# Pi2RMini_1_0.net
KiCad netlist of a schematic drawn in EAGLE
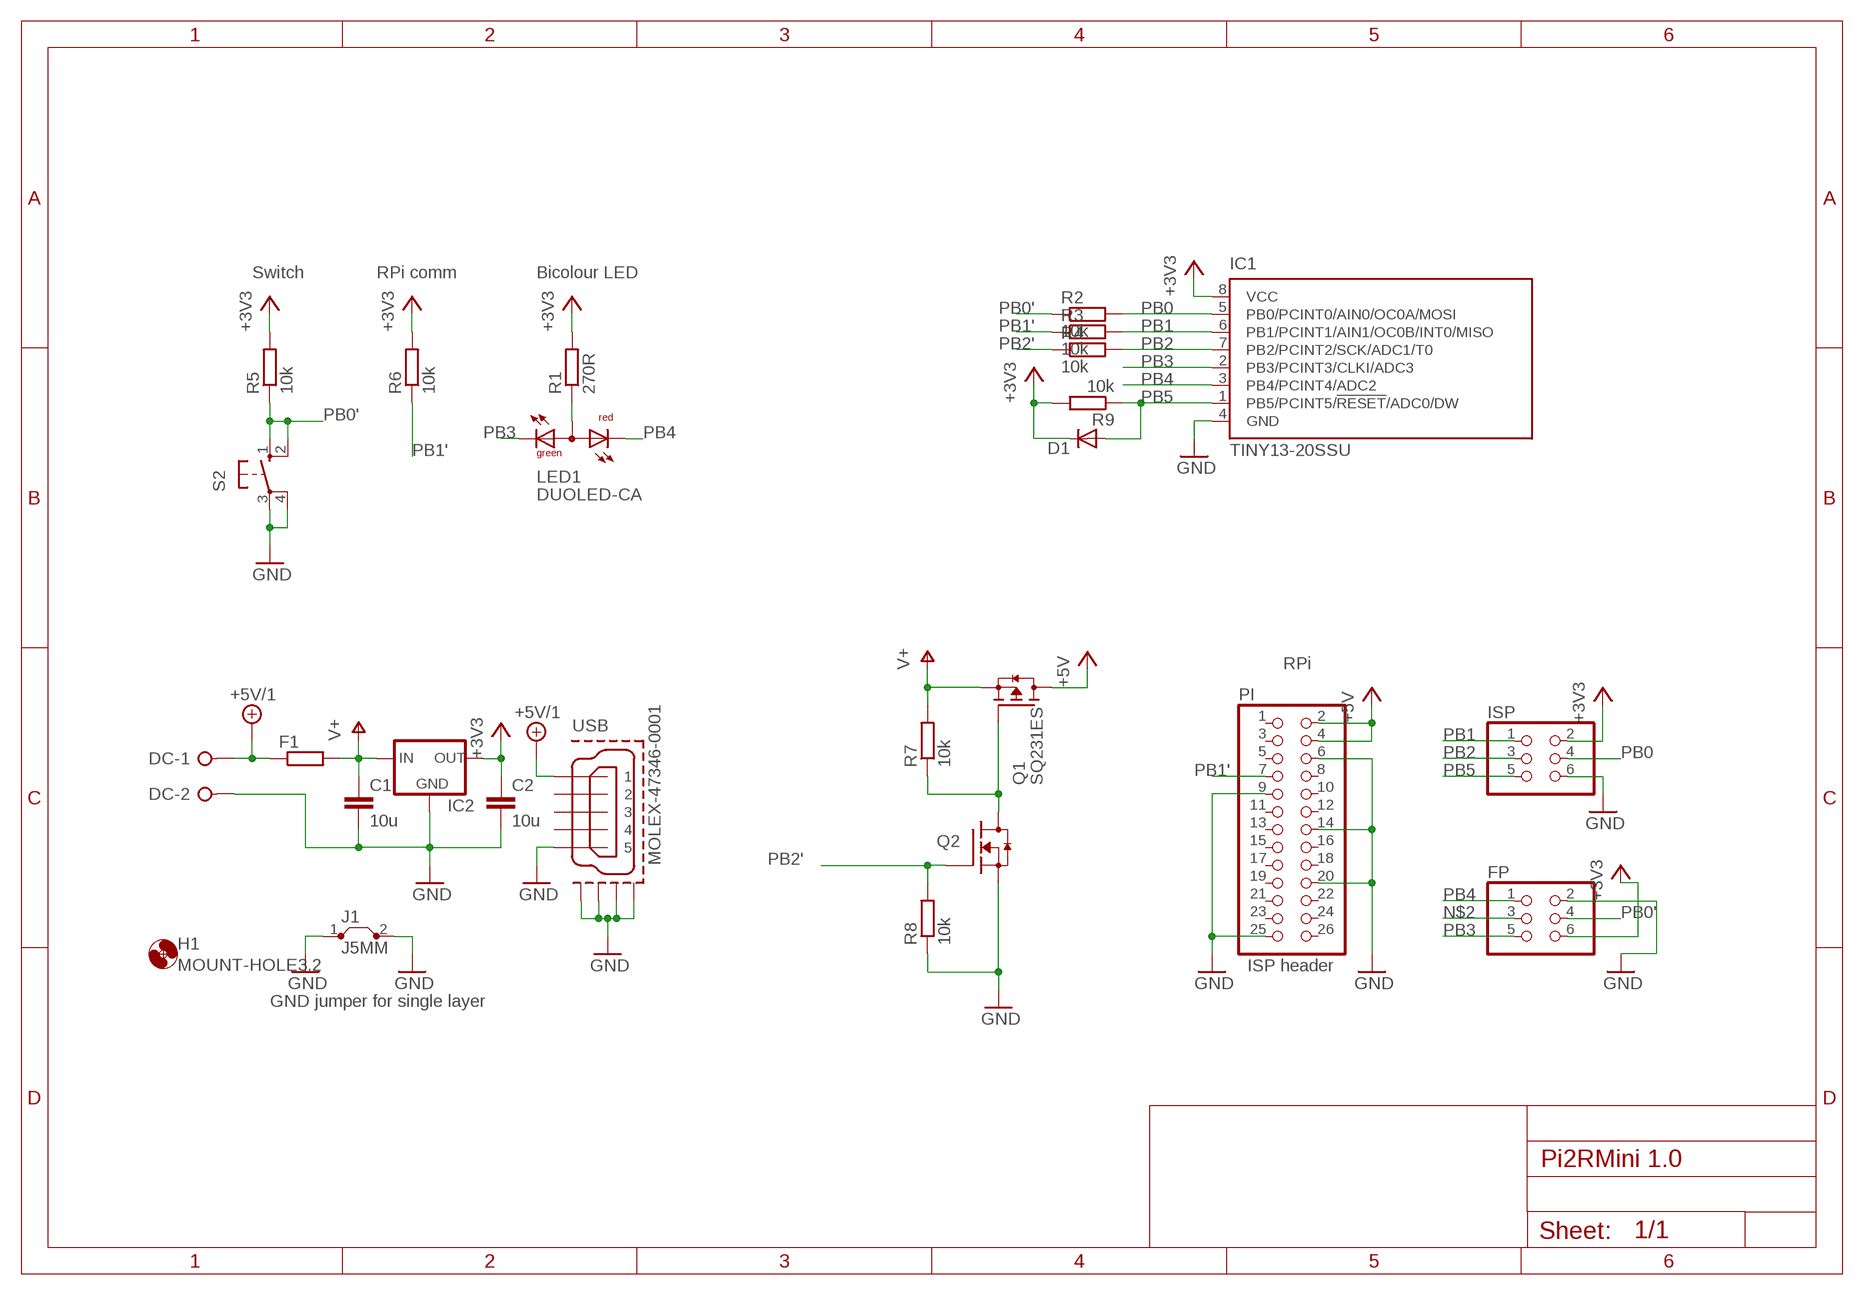
[diagram p0: schematic, sheet 1]

(export (version "E")
  (design (tool "Eeschema 10.0.6"))
  (components
    (comp (ref "C1")
      (value "10u")
      (footprint "eagle-import:C0805")
      (libsource (lib "eagle-import") (part "C-EUC0805"))
    )
    (comp (ref "C2")
      (value "10u")
      (footprint "eagle-import:C0805")
      (libsource (lib "eagle-import") (part "C-EUC0805"))
    )
    (comp (ref "D1")
      (value "DIODE-MICROMELF-R")
      (footprint "eagle-import:MICROMELF-R")
      (libsource (lib "eagle-import") (part "DIODE-MICROMELF-R"))
    )
    (comp (ref "DC")
      (value "W237-02P")
      (footprint "eagle-import:W237-132")
      (libsource (lib "eagle-import") (part "W237-02P"))
    )
    (comp (ref "F1")
      (value "R-EU_R1210")
      (footprint "eagle-import:R1210")
      (libsource (lib "eagle-import") (part "R-EU_R1210"))
    )
    (comp (ref "FP")
      (value "PINHD-2X3")
      (footprint "eagle-import:2X03")
      (libsource (lib "eagle-import") (part "PINHD-2X3"))
    )
    (comp (ref "H1")
      (value "MOUNT-HOLE3.2")
      (footprint "eagle-import:3,2")
      (libsource (lib "eagle-import") (part "MOUNT-HOLE3.2"))
    )
    (comp (ref "IC1")
      (value "TINY13-20SSU")
      (footprint "eagle-import:8S1")
      (fields (field (name "MPN") "ATTINY13-20SSU"))
      (libsource (lib "eagle-import") (part "TINY13SSU-20"))
    )
    (comp (ref "IC2")
      (value "MCP1700TT")
      (footprint "eagle-import:SOT-23")
      (libsource (lib "eagle-import") (part "MCP1700TT"))
    )
    (comp (ref "ISP")
      (value "PINHD-2X3")
      (footprint "eagle-import:2X03")
      (libsource (lib "eagle-import") (part "PINHD-2X3"))
    )
    (comp (ref "J1")
      (value "J5MM")
      (footprint "eagle-import:05")
      (libsource (lib "eagle-import") (part "J5MM"))
    )
    (comp (ref "LED1")
      (value "DUOLED-CA")
      (footprint "eagle-import:SOT-23")
      (libsource (lib "eagle-import") (part "DUOLED-CA"))
    )
    (comp (ref "PI")
      (value "PINHD-2X13")
      (footprint "eagle-import:2X13")
      (libsource (lib "eagle-import") (part "PINHD-2X13"))
    )
    (comp (ref "Q1")
      (value "SQ231ES")
      (footprint "eagle-import:SOT-23")
      (libsource (lib "eagle-import") (part "SQ231ES"))
    )
    (comp (ref "Q2")
      (value "2N7002")
      (footprint "eagle-import:SOT-23")
      (libsource (lib "eagle-import") (part "2N7002"))
    )
    (comp (ref "R1")
      (value "270R")
      (footprint "eagle-import:R0805")
      (libsource (lib "eagle-import") (part "R-EU_R0805"))
    )
    (comp (ref "R2")
      (value "10k")
      (footprint "eagle-import:R0805")
      (libsource (lib "eagle-import") (part "R-EU_R0805"))
    )
    (comp (ref "R3")
      (value "10k")
      (footprint "eagle-import:R0805")
      (libsource (lib "eagle-import") (part "R-EU_R0805"))
    )
    (comp (ref "R4")
      (value "10k")
      (footprint "eagle-import:R0805")
      (libsource (lib "eagle-import") (part "R-EU_R0805"))
    )
    (comp (ref "R5")
      (value "10k")
      (footprint "eagle-import:R0805")
      (libsource (lib "eagle-import") (part "R-EU_R0805"))
    )
    (comp (ref "R6")
      (value "10k")
      (footprint "eagle-import:R0805")
      (libsource (lib "eagle-import") (part "R-EU_R0805"))
    )
    (comp (ref "R7")
      (value "10k")
      (footprint "eagle-import:R0805")
      (libsource (lib "eagle-import") (part "R-EU_R0805"))
    )
    (comp (ref "R8")
      (value "10k")
      (footprint "eagle-import:R0805")
      (libsource (lib "eagle-import") (part "R-EU_R0805"))
    )
    (comp (ref "R9")
      (value "10k")
      (footprint "eagle-import:R0805")
      (libsource (lib "eagle-import") (part "R-EU_R0805"))
    )
    (comp (ref "S2")
      (value "10-XX")
      (footprint "eagle-import:B3F-10XX")
      (fields (field (name "MPN") "B3F-1000"))
      (libsource (lib "eagle-import") (part "10-XX"))
    )
    (comp (ref "USB")
      (value "MOLEX-47346-0001")
      (footprint "eagle-import:MOLEX-47364-0001")
      (libsource (lib "eagle-import") (part "MOLEX-47346-0001"))
    )
  )
  (nets
    (net (code "1") (name "+3V3") (class "Default")
      (node (ref "C2") (pin "1") (pinfunction "1_1") (pintype "passive"))
      (node (ref "D1") (pin "C") (pinfunction "C_C") (pintype "passive"))
      (node (ref "FP") (pin "6") (pinfunction "6_6") (pintype "passive"))
      (node (ref "IC1") (pin "8") (pinfunction "VCC_8") (pintype "power_in"))
      (node (ref "IC2") (pin "2") (pinfunction "OUT_2") (pintype "passive"))
      (node (ref "ISP") (pin "2") (pinfunction "2_2") (pintype "passive"))
      (node (ref "R1") (pin "2") (pinfunction "2_2") (pintype "passive"))
      (node (ref "R5") (pin "2") (pinfunction "2_2") (pintype "passive"))
      (node (ref "R6") (pin "2") (pinfunction "2_2") (pintype "passive"))
      (node (ref "R9") (pin "2") (pinfunction "2_2") (pintype "passive"))
    )
    (net (code "2") (name "+5V") (class "Default")
      (node (ref "PI") (pin "2") (pinfunction "2_2") (pintype "passive"))
      (node (ref "PI") (pin "4") (pinfunction "4_4") (pintype "passive"))
      (node (ref "Q1") (pin "3") (pinfunction "D_3") (pintype "passive"))
    )
    (net (code "3") (name "+5V{slash}1") (class "Default")
      (node (ref "DC") (pin "1") (pinfunction "KL_1") (pintype "passive"))
      (node (ref "F1") (pin "1") (pinfunction "1_1") (pintype "passive"))
      (node (ref "USB") (pin "1") (pinfunction "1_1") (pintype "input"))
    )
    (net (code "4") (name "/N$2") (class "Default")
      (node (ref "FP") (pin "3") (pinfunction "3_3") (pintype "passive"))
      (node (ref "LED1") (pin "3") (pinfunction "A_3") (pintype "passive"))
      (node (ref "R1") (pin "1") (pinfunction "1_1") (pintype "passive"))
    )
    (net (code "5") (name "/PB0") (class "Default")
      (node (ref "IC1") (pin "5") (pinfunction "PB0/PCINT0/AIN0/OC0A/MOSI_5") (pintype "bidirectional"))
      (node (ref "ISP") (pin "4") (pinfunction "4_4") (pintype "passive"))
      (node (ref "R2") (pin "2") (pinfunction "2_2") (pintype "passive"))
    )
    (net (code "6") (name "/PB0'") (class "Default")
      (node (ref "FP") (pin "4") (pinfunction "4_4") (pintype "passive"))
      (node (ref "R2") (pin "1") (pinfunction "1_1") (pintype "passive"))
      (node (ref "R5") (pin "1") (pinfunction "1_1") (pintype "passive"))
      (node (ref "S2") (pin "1") (pinfunction "S_1") (pintype "passive"))
      (node (ref "S2") (pin "2") (pinfunction "S1_2") (pintype "passive"))
    )
    (net (code "7") (name "/PB1") (class "Default")
      (node (ref "IC1") (pin "6") (pinfunction "PB1/PCINT1/AIN1/OC0B/INT0/MISO_6") (pintype "bidirectional"))
      (node (ref "ISP") (pin "1") (pinfunction "1_1") (pintype "passive"))
      (node (ref "R3") (pin "2") (pinfunction "2_2") (pintype "passive"))
    )
    (net (code "8") (name "/PB1'") (class "Default")
      (node (ref "PI") (pin "7") (pinfunction "7_7") (pintype "passive"))
      (node (ref "R3") (pin "1") (pinfunction "1_1") (pintype "passive"))
      (node (ref "R6") (pin "1") (pinfunction "1_1") (pintype "passive"))
    )
    (net (code "9") (name "/PB2") (class "Default")
      (node (ref "IC1") (pin "7") (pinfunction "PB2/PCINT2/SCK/ADC1/T0_7") (pintype "bidirectional"))
      (node (ref "ISP") (pin "3") (pinfunction "3_3") (pintype "passive"))
      (node (ref "R4") (pin "2") (pinfunction "2_2") (pintype "passive"))
    )
    (net (code "10") (name "/PB2'") (class "Default")
      (node (ref "Q2") (pin "1") (pinfunction "G_1") (pintype "passive"))
      (node (ref "R4") (pin "1") (pinfunction "1_1") (pintype "passive"))
      (node (ref "R8") (pin "2") (pinfunction "2_2") (pintype "passive"))
    )
    (net (code "11") (name "/PB3") (class "Default")
      (node (ref "FP") (pin "5") (pinfunction "5_5") (pintype "passive"))
      (node (ref "IC1") (pin "2") (pinfunction "PB3/PCINT3/CLKI/ADC3_2") (pintype "bidirectional"))
      (node (ref "LED1") (pin "2") (pinfunction "CG_2") (pintype "passive"))
    )
    (net (code "12") (name "/PB4") (class "Default")
      (node (ref "FP") (pin "1") (pinfunction "1_1") (pintype "passive"))
      (node (ref "IC1") (pin "3") (pinfunction "PB4/PCINT4/ADC2_3") (pintype "bidirectional"))
      (node (ref "LED1") (pin "1") (pinfunction "CR_1") (pintype "passive"))
    )
    (net (code "13") (name "/PB5") (class "Default")
      (node (ref "D1") (pin "A") (pinfunction "A_A") (pintype "passive"))
      (node (ref "IC1") (pin "1") (pinfunction "PB5/PCINT5/~{RESET}/ADC0/DW_1") (pintype "bidirectional"))
      (node (ref "ISP") (pin "5") (pinfunction "5_5") (pintype "passive"))
      (node (ref "R9") (pin "1") (pinfunction "1_1") (pintype "passive"))
    )
    (net (code "14") (name "GND") (class "Default")
      (node (ref "C1") (pin "2") (pinfunction "2_2") (pintype "passive"))
      (node (ref "C2") (pin "2") (pinfunction "2_2") (pintype "passive"))
      (node (ref "DC") (pin "2") (pinfunction "KL_2") (pintype "passive"))
      (node (ref "FP") (pin "2") (pinfunction "2_2") (pintype "passive"))
      (node (ref "IC1") (pin "4") (pinfunction "GND_4") (pintype "power_in"))
      (node (ref "IC2") (pin "1") (pinfunction "GND_1") (pintype "input"))
      (node (ref "ISP") (pin "6") (pinfunction "6_6") (pintype "passive"))
      (node (ref "J1") (pin "1") (pinfunction "1_1") (pintype "passive"))
      (node (ref "J1") (pin "2") (pinfunction "2_2") (pintype "passive"))
      (node (ref "PI") (pin "14") (pinfunction "14_14") (pintype "passive"))
      (node (ref "PI") (pin "20") (pinfunction "20_20") (pintype "passive"))
      (node (ref "PI") (pin "25") (pinfunction "25_25") (pintype "passive"))
      (node (ref "PI") (pin "6") (pinfunction "6_6") (pintype "passive"))
      (node (ref "PI") (pin "9") (pinfunction "9_9") (pintype "passive"))
      (node (ref "Q2") (pin "2") (pinfunction "S_2") (pintype "passive"))
      (node (ref "R8") (pin "1") (pinfunction "1_1") (pintype "passive"))
      (node (ref "S2") (pin "3") (pinfunction "P_3") (pintype "passive"))
      (node (ref "S2") (pin "4") (pinfunction "P1_4") (pintype "passive"))
      (node (ref "USB") (pin "5") (pinfunction "5_5") (pintype "input"))
      (node (ref "USB") (pin "GND1") (pinfunction "GND1_GND1") (pintype "bidirectional"))
      (node (ref "USB") (pin "GND2") (pinfunction "GND2_GND2") (pintype "bidirectional"))
      (node (ref "USB") (pin "GND3") (pinfunction "GND3_GND3") (pintype "bidirectional"))
      (node (ref "USB") (pin "GND4") (pinfunction "GND4_GND4") (pintype "bidirectional"))
    )
    (net (code "15") (name "Net-(Q1-G)") (class "Default")
      (node (ref "Q1") (pin "1") (pinfunction "G_1") (pintype "passive"))
      (node (ref "Q2") (pin "3") (pinfunction "D_3") (pintype "passive"))
      (node (ref "R7") (pin "1") (pinfunction "1_1") (pintype "passive"))
    )
    (net (code "16") (name "V+") (class "Default")
      (node (ref "C1") (pin "1") (pinfunction "1_1") (pintype "passive"))
      (node (ref "F1") (pin "2") (pinfunction "2_2") (pintype "passive"))
      (node (ref "IC2") (pin "3") (pinfunction "IN_3") (pintype "input"))
      (node (ref "Q1") (pin "2") (pinfunction "S_2") (pintype "passive"))
      (node (ref "R7") (pin "2") (pinfunction "2_2") (pintype "passive"))
    )
    (net (code "17") (name "unconnected-(PI-Pad1)") (class "Default")
      (node (ref "PI") (pin "1") (pinfunction "1_1") (pintype "passive"))
    )
    (net (code "18") (name "unconnected-(PI-Pad3)") (class "Default")
      (node (ref "PI") (pin "3") (pinfunction "3_3") (pintype "passive"))
    )
    (net (code "19") (name "unconnected-(PI-Pad5)") (class "Default")
      (node (ref "PI") (pin "5") (pinfunction "5_5") (pintype "passive"))
    )
    (net (code "20") (name "unconnected-(PI-Pad8)") (class "Default")
      (node (ref "PI") (pin "8") (pinfunction "8_8") (pintype "passive"))
    )
    (net (code "21") (name "unconnected-(PI-Pad10)") (class "Default")
      (node (ref "PI") (pin "10") (pinfunction "10_10") (pintype "passive"))
    )
    (net (code "22") (name "unconnected-(PI-Pad11)") (class "Default")
      (node (ref "PI") (pin "11") (pinfunction "11_11") (pintype "passive"))
    )
    (net (code "23") (name "unconnected-(PI-Pad12)") (class "Default")
      (node (ref "PI") (pin "12") (pinfunction "12_12") (pintype "passive"))
    )
    (net (code "24") (name "unconnected-(PI-Pad13)") (class "Default")
      (node (ref "PI") (pin "13") (pinfunction "13_13") (pintype "passive"))
    )
    (net (code "25") (name "unconnected-(PI-Pad15)") (class "Default")
      (node (ref "PI") (pin "15") (pinfunction "15_15") (pintype "passive"))
    )
    (net (code "26") (name "unconnected-(PI-Pad16)") (class "Default")
      (node (ref "PI") (pin "16") (pinfunction "16_16") (pintype "passive"))
    )
    (net (code "27") (name "unconnected-(PI-Pad17)") (class "Default")
      (node (ref "PI") (pin "17") (pinfunction "17_17") (pintype "passive"))
    )
    (net (code "28") (name "unconnected-(PI-Pad18)") (class "Default")
      (node (ref "PI") (pin "18") (pinfunction "18_18") (pintype "passive"))
    )
    (net (code "29") (name "unconnected-(PI-Pad19)") (class "Default")
      (node (ref "PI") (pin "19") (pinfunction "19_19") (pintype "passive"))
    )
    (net (code "30") (name "unconnected-(PI-Pad21)") (class "Default")
      (node (ref "PI") (pin "21") (pinfunction "21_21") (pintype "passive"))
    )
    (net (code "31") (name "unconnected-(PI-Pad22)") (class "Default")
      (node (ref "PI") (pin "22") (pinfunction "22_22") (pintype "passive"))
    )
    (net (code "32") (name "unconnected-(PI-Pad23)") (class "Default")
      (node (ref "PI") (pin "23") (pinfunction "23_23") (pintype "passive"))
    )
    (net (code "33") (name "unconnected-(PI-Pad24)") (class "Default")
      (node (ref "PI") (pin "24") (pinfunction "24_24") (pintype "passive"))
    )
    (net (code "34") (name "unconnected-(PI-Pad26)") (class "Default")
      (node (ref "PI") (pin "26") (pinfunction "26_26") (pintype "passive"))
    )
    (net (code "35") (name "unconnected-(USB-Pad2)") (class "Default")
      (node (ref "USB") (pin "2") (pinfunction "2_2") (pintype "input"))
    )
    (net (code "36") (name "unconnected-(USB-Pad3)") (class "Default")
      (node (ref "USB") (pin "3") (pinfunction "3_3") (pintype "input"))
    )
    (net (code "37") (name "unconnected-(USB-Pad4)") (class "Default")
      (node (ref "USB") (pin "4") (pinfunction "4_4") (pintype "input"))
    )
  )
)
